# Pool_Controller.net
KiCad netlist of a schematic drawn in EAGLE
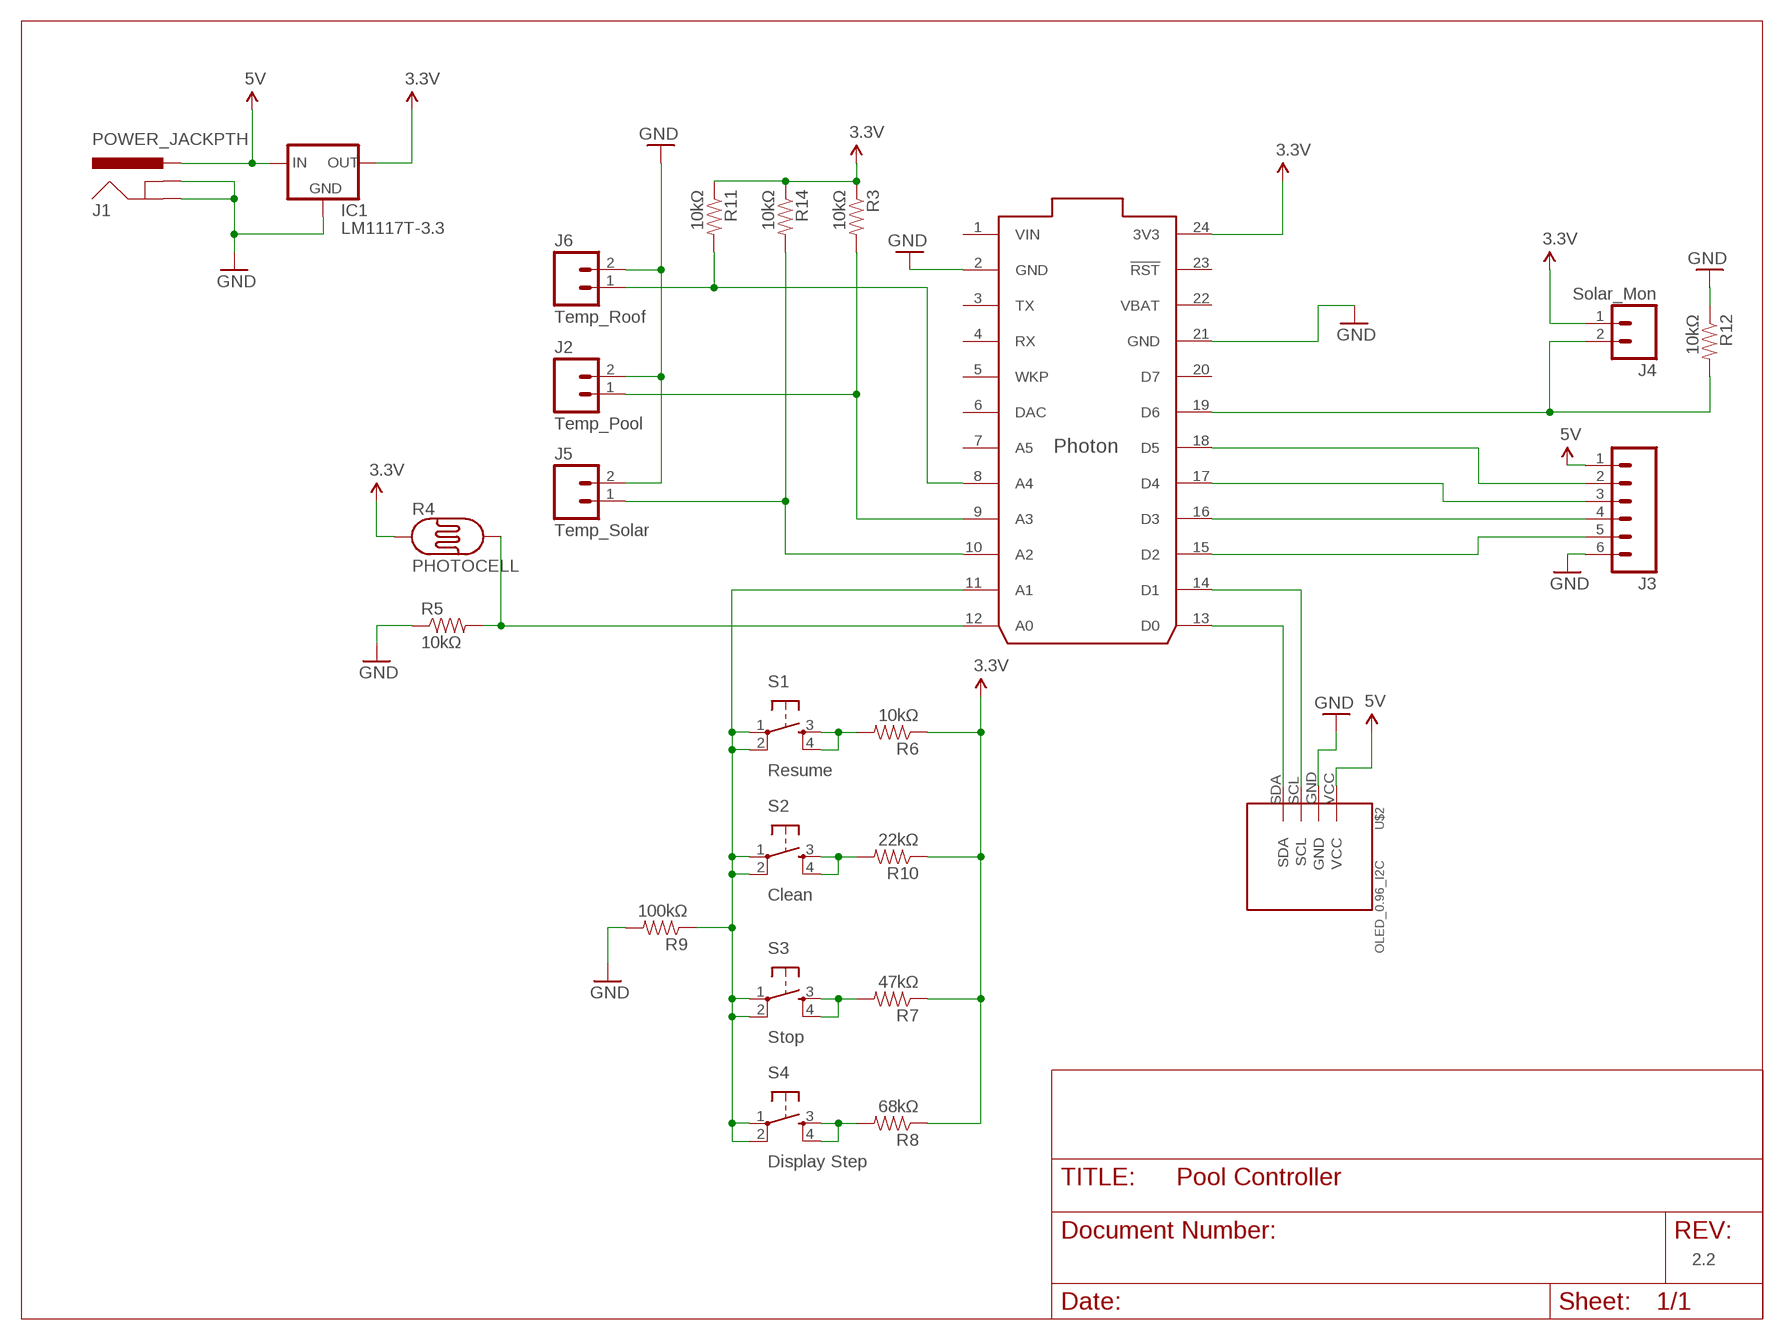
[diagram p0: schematic, sheet 1]

(export (version "E")
  (design (tool "Eeschema 10.0.6"))
  (components
    (comp (ref "IC1")
      (value "LM1117T-3.3")
      (footprint "eagle-import:TO220V")
      (libsource (lib "eagle-import") (part "LM1117T--V3.3"))
    )
    (comp (ref "J1")
      (value "POWER_JACKPTH")
      (footprint "eagle-import:POWER_JACK_PTH")
      (libsource (lib "eagle-import") (part "POWER_JACKPTH"))
    )
    (comp (ref "J2")
      (value "Temp_Pool")
      (footprint "eagle-import:SCREWTERMINAL-5MM-2")
      (libsource (lib "eagle-import") (part "M025MM"))
    )
    (comp (ref "J3")
      (value "M06SILK_FEMALE_PTH")
      (footprint "eagle-import:1X06")
      (libsource (lib "eagle-import") (part "M06SILK_FEMALE_PTH"))
    )
    (comp (ref "J4")
      (value "Solar_Mon")
      (footprint "eagle-import:SCREWTERMINAL-5MM-2")
      (libsource (lib "eagle-import") (part "M025MM"))
    )
    (comp (ref "J5")
      (value "Temp_Solar")
      (footprint "eagle-import:SCREWTERMINAL-5MM-2")
      (libsource (lib "eagle-import") (part "M025MM"))
    )
    (comp (ref "J6")
      (value "Temp_Roof")
      (footprint "eagle-import:SCREWTERMINAL-5MM-2")
      (libsource (lib "eagle-import") (part "M025MM"))
    )
    (comp (ref "PHOTON")
      (value "PHOTON_WITH_HEADERS")
      (footprint "eagle-import:PHOTON")
      (libsource (lib "eagle-import") (part "PHOTON_WITH_HEADERS"))
    )
    (comp (ref "R3")
      (value "10kΩ")
      (footprint "eagle-import:AXIAL-0.3")
      (libsource (lib "eagle-import") (part "RESISTORAXIAL-0.3"))
    )
    (comp (ref "R4")
      (value "PHOTOCELL")
      (footprint "eagle-import:PHOTOCELL")
      (libsource (lib "eagle-import") (part "PHOTOCELLPTH"))
    )
    (comp (ref "R5")
      (value "10kΩ")
      (footprint "eagle-import:AXIAL-0.3")
      (libsource (lib "eagle-import") (part "RESISTORAXIAL-0.3"))
    )
    (comp (ref "R6")
      (value "10kΩ")
      (footprint "eagle-import:AXIAL-0.3")
      (libsource (lib "eagle-import") (part "RESISTORAXIAL-0.3"))
    )
    (comp (ref "R7")
      (value "47kΩ")
      (footprint "eagle-import:AXIAL-0.3")
      (libsource (lib "eagle-import") (part "RESISTORAXIAL-0.3"))
    )
    (comp (ref "R8")
      (value "68kΩ")
      (footprint "eagle-import:AXIAL-0.3")
      (libsource (lib "eagle-import") (part "RESISTORAXIAL-0.3"))
    )
    (comp (ref "R9")
      (value "100kΩ")
      (footprint "eagle-import:AXIAL-0.3")
      (libsource (lib "eagle-import") (part "RESISTORAXIAL-0.3"))
    )
    (comp (ref "R10")
      (value "22kΩ")
      (footprint "eagle-import:AXIAL-0.3")
      (libsource (lib "eagle-import") (part "RESISTORAXIAL-0.3"))
    )
    (comp (ref "R11")
      (value "10kΩ")
      (footprint "eagle-import:AXIAL-0.3")
      (libsource (lib "eagle-import") (part "RESISTORAXIAL-0.3"))
    )
    (comp (ref "R12")
      (value "10kΩ")
      (footprint "eagle-import:AXIAL-0.3")
      (libsource (lib "eagle-import") (part "RESISTORAXIAL-0.3"))
    )
    (comp (ref "R14")
      (value "10kΩ")
      (footprint "eagle-import:AXIAL-0.3")
      (libsource (lib "eagle-import") (part "RESISTORAXIAL-0.3"))
    )
    (comp (ref "S1")
      (value "Resume")
      (footprint "eagle-import:TACTILE-PTH")
      (libsource (lib "eagle-import") (part "TAC_SWITCHPTH"))
    )
    (comp (ref "S2")
      (value "Clean")
      (footprint "eagle-import:TACTILE-PTH")
      (libsource (lib "eagle-import") (part "TAC_SWITCHPTH"))
    )
    (comp (ref "S3")
      (value "Stop")
      (footprint "eagle-import:TACTILE-PTH")
      (libsource (lib "eagle-import") (part "TAC_SWITCHPTH"))
    )
    (comp (ref "S4")
      (value "Display Step")
      (footprint "eagle-import:TACTILE-PTH")
      (libsource (lib "eagle-import") (part "TAC_SWITCHPTH"))
    )
    (comp (ref "U$2")
      (value "OLED_0.96_I2C")
      (footprint "eagle-import:OLED_0.96_I2C")
      (libsource (lib "eagle-import") (part "OLED_0.96_I2C"))
    )
  )
  (nets
    (net (code "1") (name "/VBAT") (class "Default")
      (node (ref "PHOTON") (pin "22") (pinfunction "VBAT_22") (pintype "power_in"))
    )
    (net (code "2") (name "/VIN") (class "Default")
      (node (ref "PHOTON") (pin "1") (pinfunction "VIN_1") (pintype "power_in"))
    )
    (net (code "3") (name "3.3V") (class "Default")
      (node (ref "IC1") (pin "2") (pinfunction "OUT_2") (pintype "passive"))
      (node (ref "J4") (pin "1") (pinfunction "1_1") (pintype "passive"))
      (node (ref "PHOTON") (pin "24") (pinfunction "3V3_24") (pintype "power_in"))
      (node (ref "R10") (pin "P$1") (pinfunction "1_P$1") (pintype "passive"))
      (node (ref "R11") (pin "P$1") (pinfunction "1_P$1") (pintype "passive"))
      (node (ref "R14") (pin "P$1") (pinfunction "1_P$1") (pintype "passive"))
      (node (ref "R3") (pin "P$1") (pinfunction "1_P$1") (pintype "passive"))
      (node (ref "R4") (pin "1") (pinfunction "P$1_1") (pintype "bidirectional"))
      (node (ref "R6") (pin "P$1") (pinfunction "1_P$1") (pintype "passive"))
      (node (ref "R7") (pin "P$1") (pinfunction "1_P$1") (pintype "passive"))
      (node (ref "R8") (pin "P$1") (pinfunction "1_P$1") (pintype "passive"))
    )
    (net (code "4") (name "5V") (class "Default")
      (node (ref "IC1") (pin "3") (pinfunction "IN_3") (pintype "input"))
      (node (ref "J1") (pin "PWR") (pinfunction "PWR_PWR") (pintype "bidirectional"))
      (node (ref "J3") (pin "1") (pinfunction "1_1") (pintype "passive"))
      (node (ref "U$2") (pin "VCC") (pinfunction "VCC_VCC") (pintype "bidirectional"))
    )
    (net (code "5") (name "GND") (class "Default")
      (node (ref "IC1") (pin "1") (pinfunction "GND_1") (pintype "input"))
      (node (ref "J1") (pin "GND") (pinfunction "GND_GND") (pintype "bidirectional"))
      (node (ref "J1") (pin "GNDBREAK") (pinfunction "GNDBREAK_GNDBREAK") (pintype "bidirectional"))
      (node (ref "J2") (pin "2") (pinfunction "2_2") (pintype "passive"))
      (node (ref "J3") (pin "6") (pinfunction "6_6") (pintype "passive"))
      (node (ref "J5") (pin "2") (pinfunction "2_2") (pintype "passive"))
      (node (ref "J6") (pin "2") (pinfunction "2_2") (pintype "passive"))
      (node (ref "PHOTON") (pin "2") (pinfunction "GND_2") (pintype "power_in"))
      (node (ref "PHOTON") (pin "21") (pinfunction "GND_21") (pintype "power_in"))
      (node (ref "R12") (pin "P$1") (pinfunction "1_P$1") (pintype "passive"))
      (node (ref "R5") (pin "P$1") (pinfunction "1_P$1") (pintype "passive"))
      (node (ref "R9") (pin "P$2") (pinfunction "2_P$2") (pintype "passive"))
      (node (ref "U$2") (pin "GND") (pinfunction "GND_GND") (pintype "bidirectional"))
    )
    (net (code "6") (name "Net-(PHOTON-A0)") (class "Default")
      (node (ref "PHOTON") (pin "12") (pinfunction "A0_12") (pintype "bidirectional"))
      (node (ref "R4") (pin "2") (pinfunction "P$2_2") (pintype "bidirectional"))
      (node (ref "R5") (pin "P$2") (pinfunction "2_P$2") (pintype "passive"))
    )
    (net (code "7") (name "Net-(PHOTON-A1)") (class "Default")
      (node (ref "PHOTON") (pin "11") (pinfunction "A1_11") (pintype "bidirectional"))
      (node (ref "R9") (pin "P$1") (pinfunction "1_P$1") (pintype "passive"))
      (node (ref "S1") (pin "1") (pinfunction "1_1") (pintype "passive"))
      (node (ref "S1") (pin "2") (pinfunction "2_2") (pintype "passive"))
      (node (ref "S2") (pin "1") (pinfunction "1_1") (pintype "passive"))
      (node (ref "S2") (pin "2") (pinfunction "2_2") (pintype "passive"))
      (node (ref "S3") (pin "1") (pinfunction "1_1") (pintype "passive"))
      (node (ref "S3") (pin "2") (pinfunction "2_2") (pintype "passive"))
      (node (ref "S4") (pin "1") (pinfunction "1_1") (pintype "passive"))
      (node (ref "S4") (pin "2") (pinfunction "2_2") (pintype "passive"))
    )
    (net (code "8") (name "Net-(PHOTON-A2)") (class "Default")
      (node (ref "J5") (pin "1") (pinfunction "1_1") (pintype "passive"))
      (node (ref "PHOTON") (pin "10") (pinfunction "A2_10") (pintype "bidirectional"))
      (node (ref "R14") (pin "P$2") (pinfunction "2_P$2") (pintype "passive"))
    )
    (net (code "9") (name "Net-(PHOTON-A3)") (class "Default")
      (node (ref "J2") (pin "1") (pinfunction "1_1") (pintype "passive"))
      (node (ref "PHOTON") (pin "9") (pinfunction "A3_9") (pintype "bidirectional"))
      (node (ref "R3") (pin "P$2") (pinfunction "2_P$2") (pintype "passive"))
    )
    (net (code "10") (name "Net-(PHOTON-A4)") (class "Default")
      (node (ref "J6") (pin "1") (pinfunction "1_1") (pintype "passive"))
      (node (ref "PHOTON") (pin "8") (pinfunction "A4_8") (pintype "bidirectional"))
      (node (ref "R11") (pin "P$2") (pinfunction "2_P$2") (pintype "passive"))
    )
    (net (code "11") (name "Net-(PHOTON-D0)") (class "Default")
      (node (ref "PHOTON") (pin "13") (pinfunction "D0_13") (pintype "bidirectional"))
      (node (ref "U$2") (pin "SDA") (pinfunction "SDA_SDA") (pintype "bidirectional"))
    )
    (net (code "12") (name "Net-(PHOTON-D1)") (class "Default")
      (node (ref "PHOTON") (pin "14") (pinfunction "D1_14") (pintype "bidirectional"))
      (node (ref "U$2") (pin "SCL") (pinfunction "SCL_SCL") (pintype "bidirectional"))
    )
    (net (code "13") (name "Net-(PHOTON-D2)") (class "Default")
      (node (ref "J3") (pin "5") (pinfunction "5_5") (pintype "passive"))
      (node (ref "PHOTON") (pin "15") (pinfunction "D2_15") (pintype "bidirectional"))
    )
    (net (code "14") (name "Net-(PHOTON-D3)") (class "Default")
      (node (ref "J3") (pin "4") (pinfunction "4_4") (pintype "passive"))
      (node (ref "PHOTON") (pin "16") (pinfunction "D3_16") (pintype "bidirectional"))
    )
    (net (code "15") (name "Net-(PHOTON-D4)") (class "Default")
      (node (ref "J3") (pin "3") (pinfunction "3_3") (pintype "passive"))
      (node (ref "PHOTON") (pin "17") (pinfunction "D4_17") (pintype "bidirectional"))
    )
    (net (code "16") (name "Net-(PHOTON-D5)") (class "Default")
      (node (ref "J3") (pin "2") (pinfunction "2_2") (pintype "passive"))
      (node (ref "PHOTON") (pin "18") (pinfunction "D5_18") (pintype "bidirectional"))
    )
    (net (code "17") (name "Net-(PHOTON-D6)") (class "Default")
      (node (ref "J4") (pin "2") (pinfunction "2_2") (pintype "passive"))
      (node (ref "PHOTON") (pin "19") (pinfunction "D6_19") (pintype "bidirectional"))
      (node (ref "R12") (pin "P$2") (pinfunction "2_P$2") (pintype "passive"))
    )
    (net (code "18") (name "Net-(R6-2)") (class "Default")
      (node (ref "R6") (pin "P$2") (pinfunction "2_P$2") (pintype "passive"))
      (node (ref "S1") (pin "3") (pinfunction "3_3") (pintype "passive"))
      (node (ref "S1") (pin "4") (pinfunction "4_4") (pintype "passive"))
    )
    (net (code "19") (name "Net-(R7-2)") (class "Default")
      (node (ref "R7") (pin "P$2") (pinfunction "2_P$2") (pintype "passive"))
      (node (ref "S3") (pin "3") (pinfunction "3_3") (pintype "passive"))
      (node (ref "S3") (pin "4") (pinfunction "4_4") (pintype "passive"))
    )
    (net (code "20") (name "Net-(R8-2)") (class "Default")
      (node (ref "R8") (pin "P$2") (pinfunction "2_P$2") (pintype "passive"))
      (node (ref "S4") (pin "3") (pinfunction "3_3") (pintype "passive"))
      (node (ref "S4") (pin "4") (pinfunction "4_4") (pintype "passive"))
    )
    (net (code "21") (name "Net-(R10-2)") (class "Default")
      (node (ref "R10") (pin "P$2") (pinfunction "2_P$2") (pintype "passive"))
      (node (ref "S2") (pin "3") (pinfunction "3_3") (pintype "passive"))
      (node (ref "S2") (pin "4") (pinfunction "4_4") (pintype "passive"))
    )
    (net (code "22") (name "unconnected-(PHOTON-A5-Pad7)") (class "Default")
      (node (ref "PHOTON") (pin "7") (pinfunction "A5_7") (pintype "bidirectional"))
    )
    (net (code "23") (name "unconnected-(PHOTON-D7-Pad20)") (class "Default")
      (node (ref "PHOTON") (pin "20") (pinfunction "D7_20") (pintype "bidirectional"))
    )
    (net (code "24") (name "unconnected-(PHOTON-DAC-Pad6)") (class "Default")
      (node (ref "PHOTON") (pin "6") (pinfunction "DAC_6") (pintype "bidirectional"))
    )
    (net (code "25") (name "unconnected-(PHOTON-RX-Pad4)") (class "Default")
      (node (ref "PHOTON") (pin "4") (pinfunction "RX_4") (pintype "bidirectional"))
    )
    (net (code "26") (name "unconnected-(PHOTON-TX-Pad3)") (class "Default")
      (node (ref "PHOTON") (pin "3") (pinfunction "TX_3") (pintype "bidirectional"))
    )
    (net (code "27") (name "unconnected-(PHOTON-WKP-Pad5)") (class "Default")
      (node (ref "PHOTON") (pin "5") (pinfunction "WKP_5") (pintype "bidirectional"))
    )
    (net (code "28") (name "unconnected-(PHOTON-~{RST}-Pad23)") (class "Default")
      (node (ref "PHOTON") (pin "23") (pinfunction "~{RST}_23") (pintype "bidirectional"))
    )
  )
)
